# GSM.net
KiCad netlist of a schematic drawn in Altium Designer
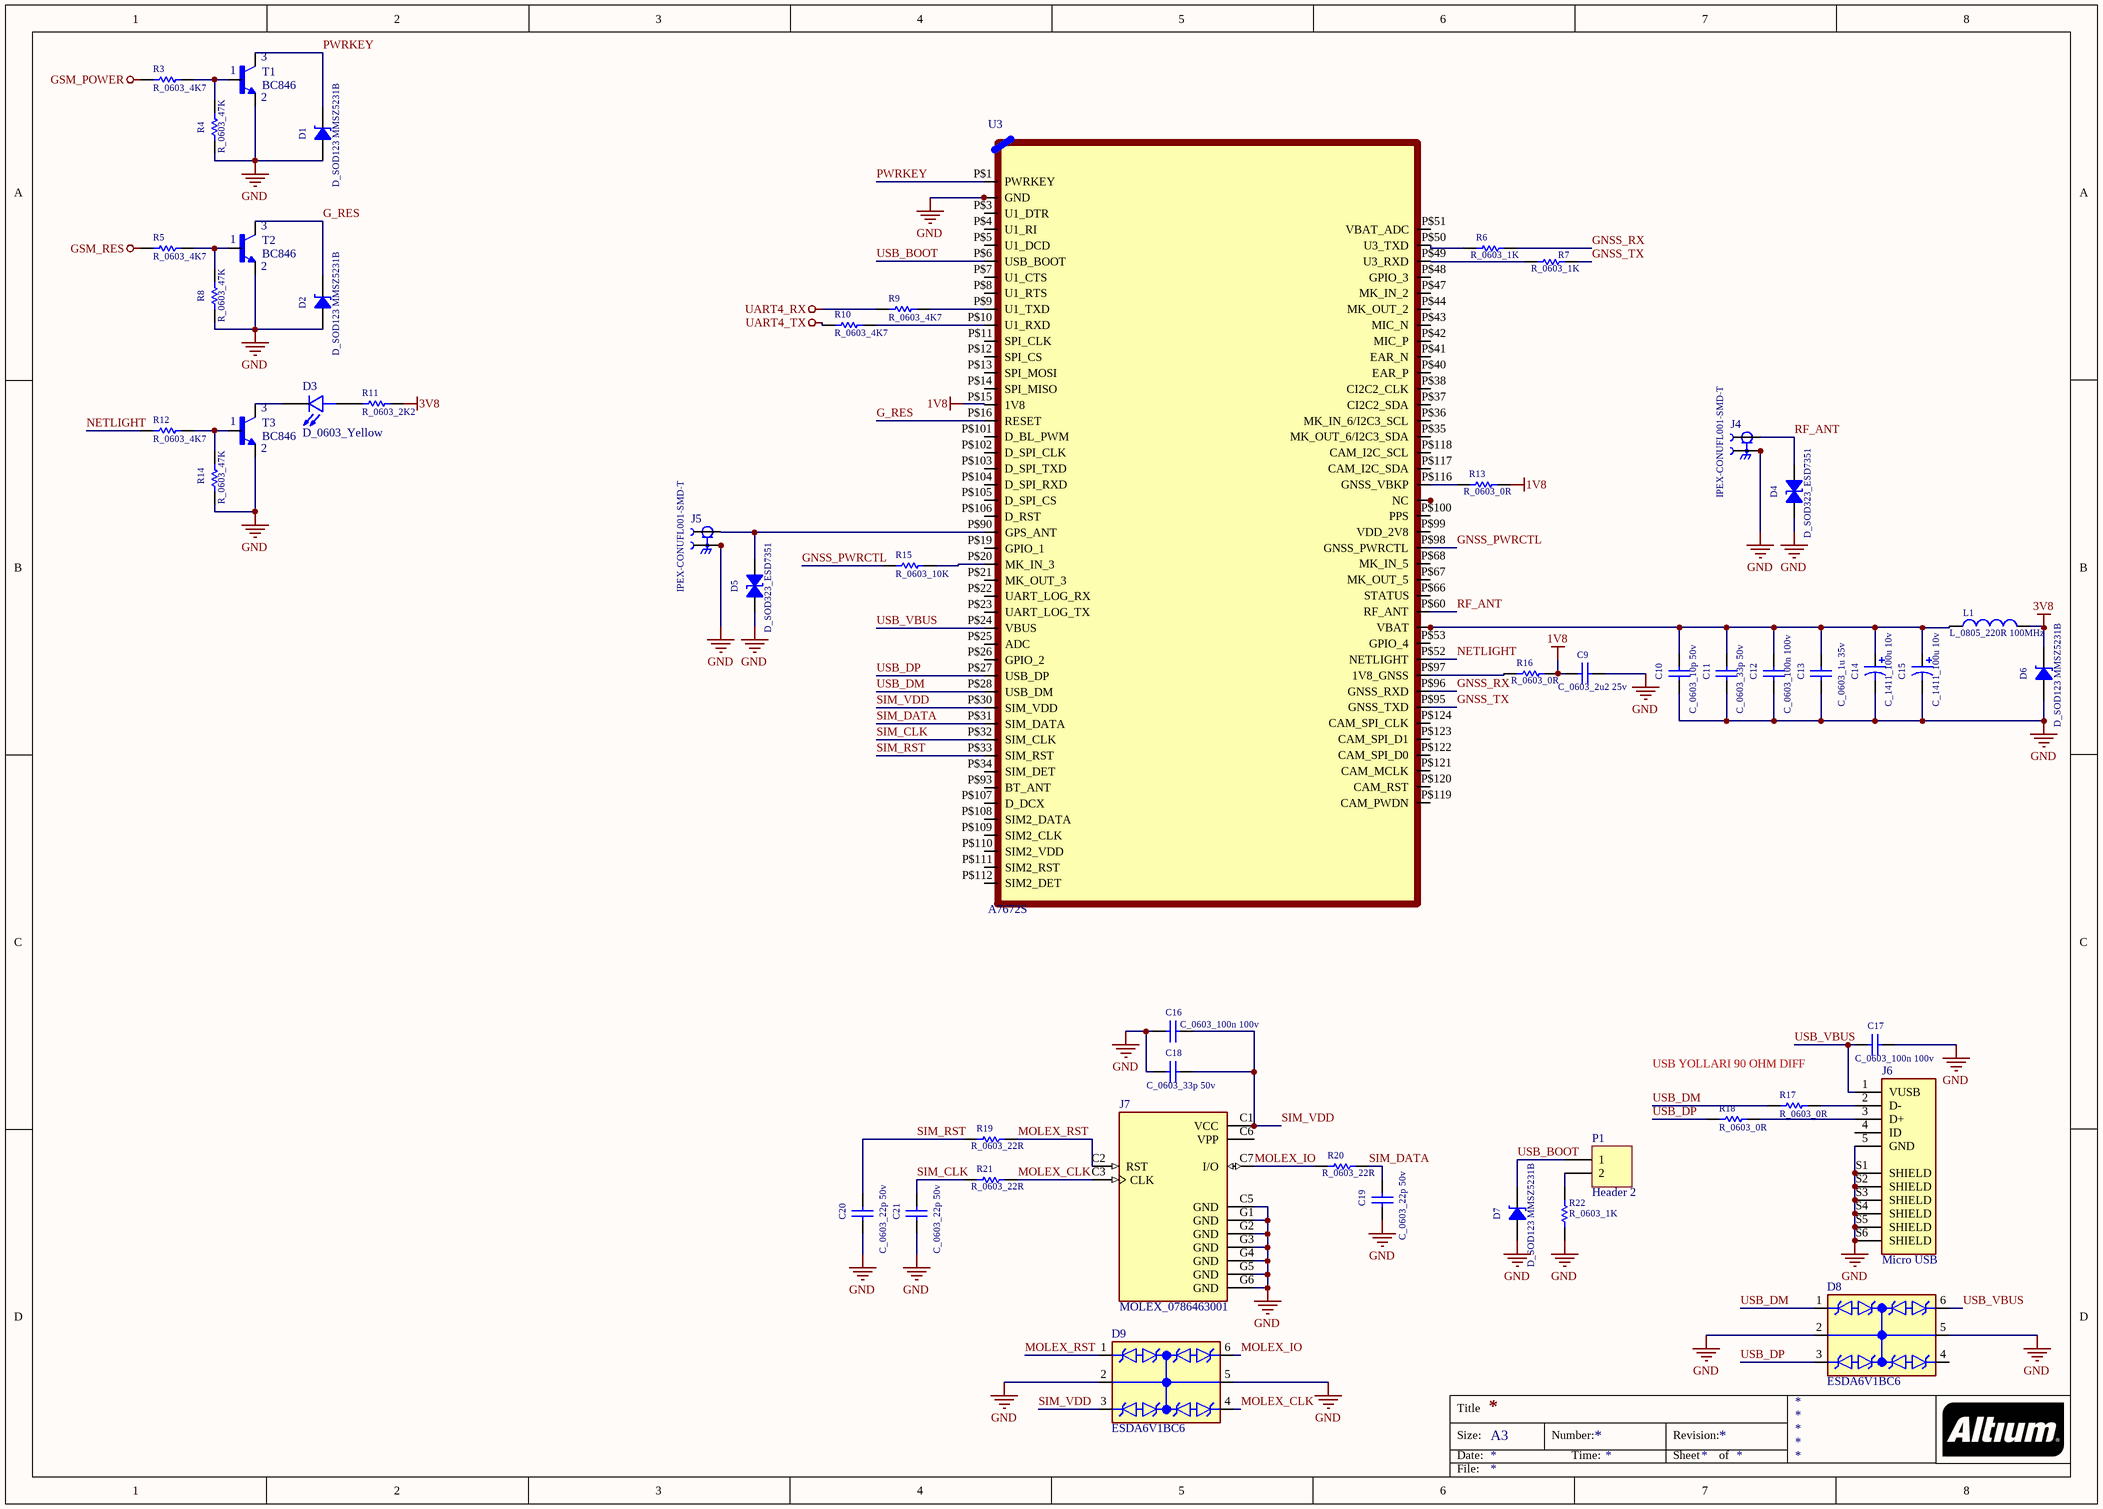
[diagram p0: GSM.SchDoc]

(export (version "E")
  (design (tool "Eeschema 10.0.6"))
  (components
    (comp (ref "C9")
      (value "C_0603_2u2 25v")
      (footprint "CAP 0603")
      (description "Capacitor")
      (fields (field (name "PUBLISHER") "Altium Limited"))
      (libsource (lib "HUE") (part "Cap"))
    )
    (comp (ref "C10")
      (value "C_0603_10p 50v")
      (footprint "CAP 0603")
      (description "Capacitor")
      (fields (field (name "PUBLISHER") "Altium Limited"))
      (libsource (lib "HUE") (part "Cap"))
    )
    (comp (ref "C11")
      (value "C_0603_33p 50v")
      (footprint "CAP 0603")
      (description "Capacitor")
      (fields (field (name "PUBLISHER") "Altium Limited"))
      (libsource (lib "HUE") (part "Cap"))
    )
    (comp (ref "C12")
      (value "C_0603_100n 100v")
      (footprint "CAP 0603")
      (description "Capacitor")
      (fields (field (name "PUBLISHER") "Altium Limited"))
      (libsource (lib "HUE") (part "Cap"))
    )
    (comp (ref "C13")
      (value "C_0603_1u 35v")
      (footprint "CAP 0603")
      (description "Capacitor")
      (fields (field (name "PUBLISHER") "Altium Limited"))
      (libsource (lib "HUE") (part "Cap"))
    )
    (comp (ref "C14")
      (value "C_1411_100u 10v")
      (footprint "CAP 1411 TAN")
      (description "Capacitor Tantalium")
      (fields (field (name "PUBLISHER") "Altium Limited"))
      (libsource (lib "HUE") (part "Cap Tantalium"))
    )
    (comp (ref "C15")
      (value "C_1411_100u 10v")
      (footprint "CAP 1411 TAN")
      (description "Capacitor Tantalium")
      (fields (field (name "PUBLISHER") "Altium Limited"))
      (libsource (lib "HUE") (part "Cap Tantalium"))
    )
    (comp (ref "C16")
      (value "C_0603_100n 100v")
      (footprint "CAP 0603")
      (description "Capacitor")
      (fields (field (name "PUBLISHER") "Altium Limited"))
      (libsource (lib "HUE") (part "Cap"))
    )
    (comp (ref "C17")
      (value "C_0603_100n 100v")
      (footprint "CAP 0603")
      (description "Capacitor")
      (fields (field (name "PUBLISHER") "Altium Limited"))
      (libsource (lib "HUE") (part "Cap"))
    )
    (comp (ref "C18")
      (value "C_0603_33p 50v")
      (footprint "CAP 0603")
      (description "Capacitor")
      (fields (field (name "PUBLISHER") "Altium Limited"))
      (libsource (lib "HUE") (part "Cap"))
    )
    (comp (ref "C19")
      (value "C_0603_22p 50v")
      (footprint "CAP 0603")
      (description "Capacitor")
      (fields (field (name "PUBLISHER") "Altium Limited"))
      (libsource (lib "HUE") (part "Cap"))
    )
    (comp (ref "C20")
      (value "C_0603_22p 50v")
      (footprint "CAP 0603")
      (description "Capacitor")
      (fields (field (name "PUBLISHER") "Altium Limited"))
      (libsource (lib "HUE") (part "Cap"))
    )
    (comp (ref "C21")
      (value "C_0603_22p 50v")
      (footprint "CAP 0603")
      (description "Capacitor")
      (fields (field (name "PUBLISHER") "Altium Limited"))
      (libsource (lib "HUE") (part "Cap"))
    )
    (comp (ref "D1")
      (value "D_SOD123 MMSZ5231B")
      (footprint "SOD-123")
      (description "Zener Diode")
      (libsource (lib "HUE") (part "Diode Zener"))
    )
    (comp (ref "D2")
      (value "D_SOD123 MMSZ5231B")
      (footprint "SOD-123")
      (description "Zener Diode")
      (libsource (lib "HUE") (part "Diode Zener"))
    )
    (comp (ref "D3")
      (value "D_0603_Yellow")
      (footprint "Led 0603")
      (description "Led")
      (fields (field (name "MP") "SML-D12FWT86") (field (name "MF") "Rohm"))
      (libsource (lib "HUE") (part "Led"))
    )
    (comp (ref "D4")
      (value "D_SOD323_ESD7351")
      (footprint "SOD323")
      (description "Zener Diode")
      (libsource (lib "HUE") (part "Diode TVS"))
    )
    (comp (ref "D5")
      (value "D_SOD323_ESD7351")
      (footprint "SOD323")
      (description "Zener Diode")
      (libsource (lib "HUE") (part "Diode TVS"))
    )
    (comp (ref "D6")
      (value "D_SOD123 MMSZ5231B")
      (footprint "SOD-123")
      (description "Zener Diode")
      (libsource (lib "HUE") (part "Diode Zener"))
    )
    (comp (ref "D7")
      (value "D_SOD123 MMSZ5231B")
      (footprint "SOD-123")
      (description "Zener Diode")
      (libsource (lib "HUE") (part "Diode Zener"))
    )
    (comp (ref "D8")
      (value "ESDA6V1BC6")
      (footprint "SOT23-6")
      (description "- Clamp - Ipp Tvs Diode Surface Mount SOT-23-6")
      (fields (field (name "MF") "STMicroelectronics"))
      (libsource (lib "HUE") (part "ESDA6V1BC6"))
    )
    (comp (ref "D9")
      (value "ESDA6V1BC6")
      (footprint "SOT23-6")
      (description "- Clamp - Ipp Tvs Diode Surface Mount SOT-23-6")
      (fields (field (name "MF") "STMicroelectronics"))
      (libsource (lib "HUE") (part "ESDA6V1BC6"))
    )
    (comp (ref "J4")
      (value "IPEX-CONUFL001-SMD-T")
      (footprint "IPEX_LINX_CONUFL001-SMD-T")
      (description "U.FL (UMCC) Connector Jack, Male Pin 50Ohm Surface Mount Solder")
      (fields (field (name "MP") "CONUFL001-SMD-T") (field (name "MF") "Linx"))
      (libsource (lib "HUE") (part "IPEX-CONUFL001-SMD-T"))
    )
    (comp (ref "J5")
      (value "IPEX-CONUFL001-SMD-T")
      (footprint "IPEX_LINX_CONUFL001-SMD-T")
      (description "U.FL (UMCC) Connector Jack, Male Pin 50Ohm Surface Mount Solder")
      (fields (field (name "MP") "CONUFL001-SMD-T") (field (name "MF") "Linx"))
      (libsource (lib "HUE") (part "IPEX-CONUFL001-SMD-T"))
    )
    (comp (ref "J6")
      (value "Micro USB")
      (footprint "Micro USB")
      (description "Micro USB 2.0, Input Output Connectors, B TYPE RECEPTACLE")
      (fields (field (name "MP") "10118193-0001LF") (field (name "MF") "Amphenol ICC"))
      (libsource (lib "HUE") (part "Micro USB"))
    )
    (comp (ref "J7")
      (value "MOLEX_0786463001")
      (footprint "MOLEX_0786463001")
      (description "6 Position Card Connector Micro SIM Surface Mount, Right Angle Gold")
      (fields (field (name "MF") "Molex") (field (name "MP") "0786463001"))
      (libsource (lib "HUE") (part "MOLEX_0786463001"))
    )
    (comp (ref "L1")
      (value "L_0805_220R 100MHz")
      (footprint "Inductor 0805")
      (description "Inductor")
      (fields (field (name "PUBLISHER") "Altium Limited"))
      (libsource (lib "HUE") (part "Inductor"))
    )
    (comp (ref "P1")
      (value "Header 2")
      (footprint "HDR1X2")
      (description "Header, 2-Pin")
      (fields (field (name "PUBLISHER") "Altium Limited"))
      (libsource (lib "Miscellaneous Connectors") (part "Header 2"))
    )
    (comp (ref "R3")
      (value "R_0603_4K7")
      (footprint "RES 0603")
      (description "Resistor")
      (fields (field (name "PUBLISHER") "Altium Limited"))
      (libsource (lib "HUE") (part "Res"))
    )
    (comp (ref "R4")
      (value "R_0603_47K")
      (footprint "RES 0603")
      (description "Resistor")
      (fields (field (name "PUBLISHER") "Altium Limited"))
      (libsource (lib "HUE") (part "Res"))
    )
    (comp (ref "R5")
      (value "R_0603_4K7")
      (footprint "RES 0603")
      (description "Resistor")
      (fields (field (name "PUBLISHER") "Altium Limited"))
      (libsource (lib "HUE") (part "Res"))
    )
    (comp (ref "R6")
      (value "R_0603_1K")
      (footprint "RES 0603")
      (description "Resistor")
      (fields (field (name "PUBLISHER") "Altium Limited"))
      (libsource (lib "HUE") (part "Res"))
    )
    (comp (ref "R7")
      (value "R_0603_1K")
      (footprint "RES 0603")
      (description "Resistor")
      (fields (field (name "PUBLISHER") "Altium Limited"))
      (libsource (lib "HUE") (part "Res"))
    )
    (comp (ref "R8")
      (value "R_0603_47K")
      (footprint "RES 0603")
      (description "Resistor")
      (fields (field (name "PUBLISHER") "Altium Limited"))
      (libsource (lib "HUE") (part "Res"))
    )
    (comp (ref "R9")
      (value "R_0603_4K7")
      (footprint "RES 0603")
      (description "Resistor")
      (fields (field (name "PUBLISHER") "Altium Limited"))
      (libsource (lib "HUE") (part "Res"))
    )
    (comp (ref "R10")
      (value "R_0603_4K7")
      (footprint "RES 0603")
      (description "Resistor")
      (fields (field (name "PUBLISHER") "Altium Limited"))
      (libsource (lib "HUE") (part "Res"))
    )
    (comp (ref "R11")
      (value "R_0603_2K2")
      (footprint "RES 0603")
      (description "Resistor")
      (fields (field (name "PUBLISHER") "Altium Limited"))
      (libsource (lib "HUE") (part "Res"))
    )
    (comp (ref "R12")
      (value "R_0603_4K7")
      (footprint "RES 0603")
      (description "Resistor")
      (fields (field (name "PUBLISHER") "Altium Limited"))
      (libsource (lib "HUE") (part "Res"))
    )
    (comp (ref "R13")
      (value "R_0603_0R")
      (footprint "RES 0603")
      (description "Resistor")
      (fields (field (name "PUBLISHER") "Altium Limited"))
      (libsource (lib "HUE") (part "Res"))
    )
    (comp (ref "R14")
      (value "R_0603_47K")
      (footprint "RES 0603")
      (description "Resistor")
      (fields (field (name "PUBLISHER") "Altium Limited"))
      (libsource (lib "HUE") (part "Res"))
    )
    (comp (ref "R15")
      (value "R_0603_10K")
      (footprint "RES 0603")
      (description "Resistor")
      (fields (field (name "PUBLISHER") "Altium Limited"))
      (libsource (lib "HUE") (part "Res"))
    )
    (comp (ref "R16")
      (value "R_0603_0R")
      (footprint "RES 0603")
      (description "Resistor")
      (fields (field (name "PUBLISHER") "Altium Limited"))
      (libsource (lib "HUE") (part "Res"))
    )
    (comp (ref "R17")
      (value "R_0603_0R")
      (footprint "RES 0603")
      (description "Resistor")
      (fields (field (name "PUBLISHER") "Altium Limited"))
      (libsource (lib "HUE") (part "Res"))
    )
    (comp (ref "R18")
      (value "R_0603_0R")
      (footprint "RES 0603")
      (description "Resistor")
      (fields (field (name "PUBLISHER") "Altium Limited"))
      (libsource (lib "HUE") (part "Res"))
    )
    (comp (ref "R19")
      (value "R_0603_22R")
      (footprint "RES 0603")
      (description "Resistor")
      (fields (field (name "PUBLISHER") "Altium Limited"))
      (libsource (lib "HUE") (part "Res"))
    )
    (comp (ref "R20")
      (value "R_0603_22R")
      (footprint "RES 0603")
      (description "Resistor")
      (fields (field (name "PUBLISHER") "Altium Limited"))
      (libsource (lib "HUE") (part "Res"))
    )
    (comp (ref "R21")
      (value "R_0603_22R")
      (footprint "RES 0603")
      (description "Resistor")
      (fields (field (name "PUBLISHER") "Altium Limited"))
      (libsource (lib "HUE") (part "Res"))
    )
    (comp (ref "R22")
      (value "R_0603_1K")
      (footprint "RES 0603")
      (description "Resistor")
      (fields (field (name "PUBLISHER") "Altium Limited"))
      (libsource (lib "HUE") (part "Res"))
    )
    (comp (ref "T1")
      (value "BC846")
      (footprint "SOT23")
      (fields (field (name "MF") "ON Semiconductor"))
      (libsource (lib "HUE") (part "BC846"))
    )
    (comp (ref "T2")
      (value "BC846")
      (footprint "SOT23")
      (fields (field (name "MF") "ON Semiconductor"))
      (libsource (lib "HUE") (part "BC846"))
    )
    (comp (ref "T3")
      (value "BC846")
      (footprint "SOT23")
      (fields (field (name "MF") "ON Semiconductor"))
      (libsource (lib "HUE") (part "BC846"))
    )
    (comp (ref "U3")
      (value "A7672S")
      (footprint "A7672S")
      (fields (field (name "MF") "SIMCom"))
      (libsource (lib "HUE") (part "A7672S"))
    )
  )
  (nets
    (net (code "1") (name "/GNSS_PWRCTL") (class "Default")
      (node (ref "R15") (pin "2") (pinfunction "2_2") (pintype "passive"))
      (node (ref "U3") (pin "P$98") (pinfunction "GNSS_PWRCTL_P$98") (pintype "bidirectional"))
    )
    (net (code "2") (name "/GNSS_RX") (class "Default")
      (node (ref "R6") (pin "1") (pinfunction "1_1") (pintype "passive"))
      (node (ref "U3") (pin "P$96") (pinfunction "GNSS_RXD_P$96") (pintype "bidirectional"))
    )
    (net (code "3") (name "/GNSS_TX") (class "Default")
      (node (ref "R7") (pin "1") (pinfunction "1_1") (pintype "passive"))
      (node (ref "U3") (pin "P$95") (pinfunction "GNSS_TXD_P$95") (pintype "bidirectional"))
    )
    (net (code "4") (name "/G_RES") (class "Default")
      (node (ref "D2") (pin "2") (pinfunction "2_2") (pintype "passive"))
      (node (ref "T2") (pin "3") (pinfunction "C_3") (pintype "passive"))
      (node (ref "U3") (pin "P$16") (pinfunction "RESET_P$16") (pintype "power_in"))
    )
    (net (code "5") (name "/MOLEX_CLK") (class "Default")
      (node (ref "D9") (pin "4") (pinfunction "C3_4") (pintype "passive"))
      (node (ref "J7") (pin "C3") (pinfunction "CLK_C3") (pintype "input"))
      (node (ref "R21") (pin "1") (pinfunction "1_1") (pintype "passive"))
    )
    (net (code "6") (name "/MOLEX_IO") (class "Default")
      (node (ref "D9") (pin "6") (pinfunction "C4_6") (pintype "passive"))
      (node (ref "J7") (pin "C7") (pinfunction "I/O_C7") (pintype "bidirectional"))
      (node (ref "R20") (pin "2") (pinfunction "2_2") (pintype "passive"))
    )
    (net (code "7") (name "/MOLEX_RST") (class "Default")
      (node (ref "D9") (pin "1") (pinfunction "C1_1") (pintype "passive"))
      (node (ref "J7") (pin "C2") (pinfunction "RST_C2") (pintype "input"))
      (node (ref "R19") (pin "1") (pinfunction "1_1") (pintype "passive"))
    )
    (net (code "8") (name "/NETLIGHT") (class "Default")
      (node (ref "R12") (pin "2") (pinfunction "2_2") (pintype "passive"))
      (node (ref "U3") (pin "P$52") (pinfunction "NETLIGHT_P$52") (pintype "bidirectional"))
    )
    (net (code "9") (name "/PWRKEY") (class "Default")
      (node (ref "D1") (pin "2") (pinfunction "2_2") (pintype "passive"))
      (node (ref "T1") (pin "3") (pinfunction "C_3") (pintype "passive"))
      (node (ref "U3") (pin "P$1") (pinfunction "PWRKEY_P$1") (pintype "power_in"))
    )
    (net (code "10") (name "/RF_ANT") (class "Default")
      (node (ref "D4") (pin "2") (pinfunction "2_2") (pintype "passive"))
      (node (ref "J4") (pin "1") (pinfunction "1_1") (pintype "passive"))
      (node (ref "U3") (pin "P$60") (pinfunction "RF_ANT_P$60") (pintype "bidirectional"))
    )
    (net (code "11") (name "/SIM_CLK") (class "Default")
      (node (ref "C21") (pin "1") (pinfunction "1_1") (pintype "passive"))
      (node (ref "R21") (pin "2") (pinfunction "2_2") (pintype "passive"))
      (node (ref "U3") (pin "P$32") (pinfunction "SIM_CLK_P$32") (pintype "bidirectional"))
    )
    (net (code "12") (name "/SIM_DATA") (class "Default")
      (node (ref "C19") (pin "1") (pinfunction "1_1") (pintype "passive"))
      (node (ref "R20") (pin "1") (pinfunction "1_1") (pintype "passive"))
      (node (ref "U3") (pin "P$31") (pinfunction "SIM_DATA_P$31") (pintype "bidirectional"))
    )
    (net (code "13") (name "/SIM_RST") (class "Default")
      (node (ref "C20") (pin "1") (pinfunction "1_1") (pintype "passive"))
      (node (ref "R19") (pin "2") (pinfunction "2_2") (pintype "passive"))
      (node (ref "U3") (pin "P$33") (pinfunction "SIM_RST_P$33") (pintype "bidirectional"))
    )
    (net (code "14") (name "/SIM_VDD") (class "Default")
      (node (ref "C16") (pin "1") (pinfunction "1_1") (pintype "passive"))
      (node (ref "C18") (pin "1") (pinfunction "1_1") (pintype "passive"))
      (node (ref "D9") (pin "3") (pinfunction "C2_3") (pintype "passive"))
      (node (ref "J7") (pin "C1") (pinfunction "VCC_C1") (pintype "power_in"))
      (node (ref "U3") (pin "P$30") (pinfunction "SIM_VDD_P$30") (pintype "bidirectional"))
    )
    (net (code "15") (name "/USB_BOOT") (class "Default")
      (node (ref "D7") (pin "2") (pinfunction "2_2") (pintype "passive"))
      (node (ref "P1") (pin "1") (pinfunction "1_1") (pintype "passive"))
      (node (ref "U3") (pin "P$6") (pinfunction "USB_BOOT_P$6") (pintype "bidirectional"))
    )
    (net (code "16") (name "/USB_DM") (class "Default")
      (node (ref "D8") (pin "1") (pinfunction "C1_1") (pintype "passive"))
      (node (ref "R17") (pin "2") (pinfunction "2_2") (pintype "passive"))
      (node (ref "U3") (pin "P$28") (pinfunction "USB_DM_P$28") (pintype "bidirectional"))
    )
    (net (code "17") (name "/USB_DP") (class "Default")
      (node (ref "D8") (pin "3") (pinfunction "C2_3") (pintype "passive"))
      (node (ref "R18") (pin "2") (pinfunction "2_2") (pintype "passive"))
      (node (ref "U3") (pin "P$27") (pinfunction "USB_DP_P$27") (pintype "bidirectional"))
    )
    (net (code "18") (name "/USB_VBUS") (class "Default")
      (node (ref "C17") (pin "2") (pinfunction "2_2") (pintype "passive"))
      (node (ref "D8") (pin "6") (pinfunction "C4_6") (pintype "passive"))
      (node (ref "J6") (pin "1") (pinfunction "VUSB_1") (pintype "passive"))
      (node (ref "U3") (pin "P$24") (pinfunction "VBUS_P$24") (pintype "bidirectional"))
    )
    (net (code "19") (name "1V8") (class "Default")
      (node (ref "C9") (pin "1") (pinfunction "1_1") (pintype "passive"))
      (node (ref "R13") (pin "1") (pinfunction "1_1") (pintype "passive"))
      (node (ref "R16") (pin "1") (pinfunction "1_1") (pintype "passive"))
      (node (ref "U3") (pin "P$15") (pinfunction "1V8_P$15") (pintype "power_in"))
    )
    (net (code "20") (name "3V8") (class "Default")
      (node (ref "D6") (pin "2") (pinfunction "2_2") (pintype "passive"))
      (node (ref "L1") (pin "2") (pinfunction "2_2") (pintype "passive"))
      (node (ref "R11") (pin "2") (pinfunction "2_2") (pintype "passive"))
    )
    (net (code "21") (name "GND") (class "Default")
      (node (ref "C10") (pin "1") (pinfunction "1_1") (pintype "passive"))
      (node (ref "C11") (pin "1") (pinfunction "1_1") (pintype "passive"))
      (node (ref "C12") (pin "1") (pinfunction "1_1") (pintype "passive"))
      (node (ref "C13") (pin "2") (pinfunction "2_2") (pintype "passive"))
      (node (ref "C14") (pin "2") (pinfunction "2_2") (pintype "passive"))
      (node (ref "C15") (pin "2") (pinfunction "2_2") (pintype "passive"))
      (node (ref "C16") (pin "2") (pinfunction "2_2") (pintype "passive"))
      (node (ref "C17") (pin "1") (pinfunction "1_1") (pintype "passive"))
      (node (ref "C18") (pin "2") (pinfunction "2_2") (pintype "passive"))
      (node (ref "C19") (pin "2") (pinfunction "2_2") (pintype "passive"))
      (node (ref "C20") (pin "2") (pinfunction "2_2") (pintype "passive"))
      (node (ref "C21") (pin "2") (pinfunction "2_2") (pintype "passive"))
      (node (ref "C9") (pin "2") (pinfunction "2_2") (pintype "passive"))
      (node (ref "D1") (pin "1") (pinfunction "1_1") (pintype "passive"))
      (node (ref "D2") (pin "1") (pinfunction "1_1") (pintype "passive"))
      (node (ref "D4") (pin "1") (pinfunction "1_1") (pintype "passive"))
      (node (ref "D5") (pin "1") (pinfunction "1_1") (pintype "passive"))
      (node (ref "D6") (pin "1") (pinfunction "1_1") (pintype "passive"))
      (node (ref "D7") (pin "1") (pinfunction "1_1") (pintype "passive"))
      (node (ref "D8") (pin "2") (pinfunction "CC1_2") (pintype "passive"))
      (node (ref "D8") (pin "5") (pinfunction "CC2_5") (pintype "passive"))
      (node (ref "D9") (pin "2") (pinfunction "CC1_2") (pintype "passive"))
      (node (ref "D9") (pin "5") (pinfunction "CC2_5") (pintype "passive"))
      (node (ref "J4") (pin "2") (pinfunction "2_2") (pintype "passive"))
      (node (ref "J4") (pin "3") (pinfunction "2_3") (pintype "passive"))
      (node (ref "J5") (pin "2") (pinfunction "2_2") (pintype "passive"))
      (node (ref "J5") (pin "3") (pinfunction "2_3") (pintype "passive"))
      (node (ref "J6") (pin "5") (pinfunction "GND_5") (pintype "passive"))
      (node (ref "J6") (pin "S1") (pinfunction "SHIELD_S1") (pintype "passive"))
      (node (ref "J6") (pin "S2") (pinfunction "SHIELD_S2") (pintype "passive"))
      (node (ref "J6") (pin "S3") (pinfunction "SHIELD_S3") (pintype "passive"))
      (node (ref "J6") (pin "S4") (pinfunction "SHIELD_S4") (pintype "passive"))
      (node (ref "J6") (pin "S5") (pinfunction "SHIELD_S5") (pintype "passive"))
      (node (ref "J6") (pin "S6") (pinfunction "SHIELD_S6") (pintype "passive"))
      (node (ref "J7") (pin "C5") (pinfunction "GND_C5") (pintype "power_in"))
      (node (ref "J7") (pin "G1") (pinfunction "GND_G1") (pintype "power_in"))
      (node (ref "J7") (pin "G2") (pinfunction "GND_G2") (pintype "power_in"))
      (node (ref "J7") (pin "G3") (pinfunction "GND_G3") (pintype "power_in"))
      (node (ref "J7") (pin "G4") (pinfunction "GND_G4") (pintype "power_in"))
      (node (ref "J7") (pin "G5") (pinfunction "GND_G5") (pintype "power_in"))
      (node (ref "J7") (pin "G6") (pinfunction "GND_G6") (pintype "power_in"))
      (node (ref "R14") (pin "2") (pinfunction "2_2") (pintype "passive"))
      (node (ref "R22") (pin "2") (pinfunction "2_2") (pintype "passive"))
      (node (ref "R4") (pin "2") (pinfunction "2_2") (pintype "passive"))
      (node (ref "R8") (pin "2") (pinfunction "2_2") (pintype "passive"))
      (node (ref "T1") (pin "2") (pinfunction "E_2") (pintype "passive"))
      (node (ref "T2") (pin "2") (pinfunction "E_2") (pintype "passive"))
      (node (ref "T3") (pin "2") (pinfunction "E_2") (pintype "passive"))
      (node (ref "U3") (pin "P$17") (pinfunction "GND_P$17") (pintype "power_in"))
      (node (ref "U3") (pin "P$18") (pinfunction "GND_P$18") (pintype "power_in"))
      (node (ref "U3") (pin "P$2") (pinfunction "GND_P$2") (pintype "power_in"))
      (node (ref "U3") (pin "P$29") (pinfunction "GND_P$29") (pintype "power_in"))
      (node (ref "U3") (pin "P$39") (pinfunction "GND_P$39") (pintype "power_in"))
      (node (ref "U3") (pin "P$45") (pinfunction "GND_P$45") (pintype "power_in"))
      (node (ref "U3") (pin "P$46") (pinfunction "GND_P$46") (pintype "power_in"))
      (node (ref "U3") (pin "P$54") (pinfunction "GND_P$54") (pintype "power_in"))
      (node (ref "U3") (pin "P$58") (pinfunction "GND_P$58") (pintype "power_in"))
      (node (ref "U3") (pin "P$59") (pinfunction "GND_P$59") (pintype "power_in"))
      (node (ref "U3") (pin "P$61") (pinfunction "GND_P$61") (pintype "power_in"))
      (node (ref "U3") (pin "P$62") (pinfunction "GND_P$62") (pintype "power_in"))
      (node (ref "U3") (pin "P$63") (pinfunction "GND_P$63") (pintype "power_in"))
      (node (ref "U3") (pin "P$64") (pinfunction "GND_P$64") (pintype "power_in"))
      (node (ref "U3") (pin "P$65") (pinfunction "GND_P$65") (pintype "power_in"))
      (node (ref "U3") (pin "P$69") (pinfunction "GND_P$69") (pintype "power_in"))
      (node (ref "U3") (pin "P$70") (pinfunction "GND_P$70") (pintype "power_in"))
      (node (ref "U3") (pin "P$71") (pinfunction "GND_P$71") (pintype "power_in"))
      (node (ref "U3") (pin "P$72") (pinfunction "GND_P$72") (pintype "power_in"))
      (node (ref "U3") (pin "P$73") (pinfunction "GND_P$73") (pintype "power_in"))
      (node (ref "U3") (pin "P$74") (pinfunction "GND_P$74") (pintype "power_in"))
      (node (ref "U3") (pin "P$75") (pinfunction "GND_P$75") (pintype "power_in"))
      (node (ref "U3") (pin "P$76") (pinfunction "GND_P$76") (pintype "power_in"))
      (node (ref "U3") (pin "P$77") (pinfunction "GND_P$77") (pintype "power_in"))
      (node (ref "U3") (pin "P$78") (pinfunction "GND_P$78") (pintype "power_in"))
      (node (ref "U3") (pin "P$79") (pinfunction "GND_P$79") (pintype "power_in"))
      (node (ref "U3") (pin "P$80") (pinfunction "GND_P$80") (pintype "power_in"))
      (node (ref "U3") (pin "P$81") (pinfunction "GND_P$81") (pintype "power_in"))
      (node (ref "U3") (pin "P$82") (pinfunction "GND_P$82") (pintype "power_in"))
      (node (ref "U3") (pin "P$83") (pinfunction "GND_P$83") (pintype "power_in"))
      (node (ref "U3") (pin "P$84") (pinfunction "GND_P$84") (pintype "power_in"))
      (node (ref "U3") (pin "P$85") (pinfunction "GND_P$85") (pintype "power_in"))
      (node (ref "U3") (pin "P$86") (pinfunction "GND_P$86") (pintype "power_in"))
      (node (ref "U3") (pin "P$87") (pinfunction "GND_P$87") (pintype "power_in"))
      (node (ref "U3") (pin "P$88") (pinfunction "GND_P$88") (pintype "power_in"))
      (node (ref "U3") (pin "P$89") (pinfunction "GND_P$89") (pintype "power_in"))
      (node (ref "U3") (pin "P$91") (pinfunction "GND_P$91") (pintype "power_in"))
      (node (ref "U3") (pin "P$92") (pinfunction "GND_P$92") (pintype "power_in"))
      (node (ref "U3") (pin "P$94") (pinfunction "GND_P$94") (pintype "power_in"))
    )
    (net (code "22") (name "GSM_POWER") (class "Default")
      (node (ref "R3") (pin "2") (pinfunction "2_2") (pintype "passive"))
    )
    (net (code "23") (name "GSM_RES") (class "Default")
      (node (ref "R5") (pin "2") (pinfunction "2_2") (pintype "passive"))
    )
    (net (code "24") (name "Net-(C10-Pad2)") (class "Default")
      (node (ref "C10") (pin "2") (pinfunction "2_2") (pintype "passive"))
      (node (ref "C11") (pin "2") (pinfunction "2_2") (pintype "passive"))
      (node (ref "C12") (pin "2") (pinfunction "2_2") (pintype "passive"))
      (node (ref "C13") (pin "1") (pinfunction "1_1") (pintype "passive"))
      (node (ref "C14") (pin "1") (pinfunction "1_1") (pintype "passive"))
      (node (ref "C15") (pin "1") (pinfunction "1_1") (pintype "passive"))
      (node (ref "L1") (pin "1") (pinfunction "1_1") (pintype "passive"))
      (node (ref "U3") (pin "P$55") (pinfunction "VBAT_P$55") (pintype "bidirectional"))
      (node (ref "U3") (pin "P$56") (pinfunction "VBAT_P$56") (pintype "bidirectional"))
      (node (ref "U3") (pin "P$57") (pinfunction "VBAT_P$57") (pintype "bidirectional"))
    )
    (net (code "25") (name "Net-(D3-A)") (class "Default")
      (node (ref "D3") (pin "1") (pinfunction "A_1") (pintype "passive"))
      (node (ref "R11") (pin "1") (pinfunction "1_1") (pintype "passive"))
    )
    (net (code "26") (name "Net-(D3-C)") (class "Default")
      (node (ref "D3") (pin "2") (pinfunction "C_2") (pintype "passive"))
      (node (ref "T3") (pin "3") (pinfunction "C_3") (pintype "passive"))
    )
    (net (code "27") (name "Net-(J6-D+)") (class "Default")
      (node (ref "J6") (pin "3") (pinfunction "D+_3") (pintype "passive"))
      (node (ref "R18") (pin "1") (pinfunction "1_1") (pintype "passive"))
    )
    (net (code "28") (name "Net-(J6-D-)") (class "Default")
      (node (ref "J6") (pin "2") (pinfunction "D-_2") (pintype "passive"))
      (node (ref "R17") (pin "1") (pinfunction "1_1") (pintype "passive"))
    )
    (net (code "29") (name "Net-(P1-Pad2)") (class "Default")
      (node (ref "P1") (pin "2") (pinfunction "2_2") (pintype "passive"))
      (node (ref "R22") (pin "1") (pinfunction "1_1") (pintype "passive"))
    )
    (net (code "30") (name "Net-(T1-B)") (class "Default")
      (node (ref "R3") (pin "1") (pinfunction "1_1") (pintype "passive"))
      (node (ref "R4") (pin "1") (pinfunction "1_1") (pintype "passive"))
      (node (ref "T1") (pin "1") (pinfunction "B_1") (pintype "passive"))
    )
    (net (code "31") (name "Net-(T2-B)") (class "Default")
      (node (ref "R5") (pin "1") (pinfunction "1_1") (pintype "passive"))
      (node (ref "R8") (pin "1") (pinfunction "1_1") (pintype "passive"))
      (node (ref "T2") (pin "1") (pinfunction "B_1") (pintype "passive"))
    )
    (net (code "32") (name "Net-(T3-B)") (class "Default")
      (node (ref "R12") (pin "1") (pinfunction "1_1") (pintype "passive"))
      (node (ref "R14") (pin "1") (pinfunction "1_1") (pintype "passive"))
      (node (ref "T3") (pin "1") (pinfunction "B_1") (pintype "passive"))
    )
    (net (code "33") (name "Net-(U3-1V8_GNSS)") (class "Default")
      (node (ref "R16") (pin "2") (pinfunction "2_2") (pintype "passive"))
      (node (ref "U3") (pin "P$97") (pinfunction "1V8_GNSS_P$97") (pintype "bidirectional"))
    )
    (net (code "34") (name "Net-(U3-GNSS_VBKP)") (class "Default")
      (node (ref "R13") (pin "2") (pinfunction "2_2") (pintype "passive"))
      (node (ref "U3") (pin "P$116") (pinfunction "GNSS_VBKP_P$116") (pintype "bidirectional"))
    )
    (net (code "35") (name "Net-(U3-GPS_ANT)") (class "Default")
      (node (ref "D5") (pin "2") (pinfunction "2_2") (pintype "passive"))
      (node (ref "J5") (pin "1") (pinfunction "1_1") (pintype "passive"))
      (node (ref "U3") (pin "P$90") (pinfunction "GPS_ANT_P$90") (pintype "bidirectional"))
    )
    (net (code "36") (name "Net-(U3-MK_IN_3)") (class "Default")
      (node (ref "R15") (pin "1") (pinfunction "1_1") (pintype "passive"))
      (node (ref "U3") (pin "P$20") (pinfunction "MK_IN_3_P$20") (pintype "bidirectional"))
    )
    (net (code "37") (name "Net-(U3-NC-PadP$113)") (class "Default")
      (node (ref "U3") (pin "P$113") (pinfunction "NC_P$113") (pintype "bidirectional"))
      (node (ref "U3") (pin "P$114") (pinfunction "NC_P$114") (pintype "bidirectional"))
      (node (ref "U3") (pin "P$115") (pinfunction "NC_P$115") (pintype "bidirectional"))
    )
    (net (code "38") (name "Net-(U3-U1_RXD)") (class "Default")
      (node (ref "R10") (pin "1") (pinfunction "1_1") (pintype "passive"))
      (node (ref "U3") (pin "P$10") (pinfunction "U1_RXD_P$10") (pintype "bidirectional"))
    )
    (net (code "39") (name "Net-(U3-U1_TXD)") (class "Default")
      (node (ref "R9") (pin "1") (pinfunction "1_1") (pintype "passive"))
      (node (ref "U3") (pin "P$9") (pinfunction "U1_TXD_P$9") (pintype "bidirectional"))
    )
    (net (code "40") (name "Net-(U3-U3_RXD)") (class "Default")
      (node (ref "R7") (pin "2") (pinfunction "2_2") (pintype "passive"))
      (node (ref "U3") (pin "P$49") (pinfunction "U3_RXD_P$49") (pintype "bidirectional"))
    )
    (net (code "41") (name "Net-(U3-U3_TXD)") (class "Default")
      (node (ref "R6") (pin "2") (pinfunction "2_2") (pintype "passive"))
      (node (ref "U3") (pin "P$50") (pinfunction "U3_TXD_P$50") (pintype "bidirectional"))
    )
    (net (code "42") (name "UART4_RX") (class "Default")
      (node (ref "R9") (pin "2") (pinfunction "2_2") (pintype "passive"))
    )
    (net (code "43") (name "UART4_TX") (class "Default")
      (node (ref "R10") (pin "2") (pinfunction "2_2") (pintype "passive"))
    )
    (net (code "44") (name "unconnected-(D8-C3-Pad4)") (class "Default")
      (node (ref "D8") (pin "4") (pinfunction "C3_4") (pintype "passive"))
    )
    (net (code "45") (name "unconnected-(J6-ID-Pad4)") (class "Default")
      (node (ref "J6") (pin "4") (pinfunction "ID_4") (pintype "passive"))
    )
    (net (code "46") (name "unconnected-(J7-VPP-PadC6)") (class "Default")
      (node (ref "J7") (pin "C6") (pinfunction "VPP_C6") (pintype "power_in"))
    )
    (net (code "47") (name "unconnected-(U3-ADC-PadP$25)") (class "Default")
      (node (ref "U3") (pin "P$25") (pinfunction "ADC_P$25") (pintype "bidirectional"))
    )
    (net (code "48") (name "unconnected-(U3-BT_ANT-PadP$93)") (class "Default")
      (node (ref "U3") (pin "P$93") (pinfunction "BT_ANT_P$93") (pintype "bidirectional"))
    )
    (net (code "49") (name "unconnected-(U3-CAM_I2C_SCL-PadP$118)") (class "Default")
      (node (ref "U3") (pin "P$118") (pinfunction "CAM_I2C_SCL_P$118") (pintype "bidirectional"))
    )
    (net (code "50") (name "unconnected-(U3-CAM_I2C_SDA-PadP$117)") (class "Default")
      (node (ref "U3") (pin "P$117") (pinfunction "CAM_I2C_SDA_P$117") (pintype "bidirectional"))
    )
    (net (code "51") (name "unconnected-(U3-CAM_MCLK-PadP$121)") (class "Default")
      (node (ref "U3") (pin "P$121") (pinfunction "CAM_MCLK_P$121") (pintype "bidirectional"))
    )
    (net (code "52") (name "unconnected-(U3-CAM_PWDN-PadP$119)") (class "Default")
      (node (ref "U3") (pin "P$119") (pinfunction "CAM_PWDN_P$119") (pintype "bidirectional"))
    )
    (net (code "53") (name "unconnected-(U3-CAM_RST-PadP$120)") (class "Default")
      (node (ref "U3") (pin "P$120") (pinfunction "CAM_RST_P$120") (pintype "bidirectional"))
    )
    (net (code "54") (name "unconnected-(U3-CAM_SPI_CLK-PadP$124)") (class "Default")
      (node (ref "U3") (pin "P$124") (pinfunction "CAM_SPI_CLK_P$124") (pintype "bidirectional"))
    )
    (net (code "55") (name "unconnected-(U3-CAM_SPI_D0-PadP$122)") (class "Default")
      (node (ref "U3") (pin "P$122") (pinfunction "CAM_SPI_D0_P$122") (pintype "bidirectional"))
    )
    (net (code "56") (name "unconnected-(U3-CAM_SPI_D1-PadP$123)") (class "Default")
      (node (ref "U3") (pin "P$123") (pinfunction "CAM_SPI_D1_P$123") (pintype "bidirectional"))
    )
    (net (code "57") (name "unconnected-(U3-CI2C2_CLK-PadP$38)") (class "Default")
      (node (ref "U3") (pin "P$38") (pinfunction "CI2C2_CLK_P$38") (pintype "bidirectional"))
    )
    (net (code "58") (name "unconnected-(U3-CI2C2_SDA-PadP$37)") (class "Default")
      (node (ref "U3") (pin "P$37") (pinfunction "CI2C2_SDA_P$37") (pintype "bidirectional"))
    )
    (net (code "59") (name "unconnected-(U3-D_BL_PWM-PadP$101)") (class "Default")
      (node (ref "U3") (pin "P$101") (pinfunction "D_BL_PWM_P$101") (pintype "bidirectional"))
    )
    (net (code "60") (name "unconnected-(U3-D_DCX-PadP$107)") (class "Default")
      (node (ref "U3") (pin "P$107") (pinfunction "D_DCX_P$107") (pintype "bidirectional"))
    )
    (net (code "61") (name "unconnected-(U3-D_RST-PadP$106)") (class "Default")
      (node (ref "U3") (pin "P$106") (pinfunction "D_RST_P$106") (pintype "bidirectional"))
    )
    (net (code "62") (name "unconnected-(U3-D_SPI_CLK-PadP$102)") (class "Default")
      (node (ref "U3") (pin "P$102") (pinfunction "D_SPI_CLK_P$102") (pintype "bidirectional"))
    )
    (net (code "63") (name "unconnected-(U3-D_SPI_CS-PadP$105)") (class "Default")
      (node (ref "U3") (pin "P$105") (pinfunction "D_SPI_CS_P$105") (pintype "bidirectional"))
    )
    (net (code "64") (name "unconnected-(U3-D_SPI_RXD-PadP$104)") (class "Default")
      (node (ref "U3") (pin "P$104") (pinfunction "D_SPI_RXD_P$104") (pintype "bidirectional"))
    )
    (net (code "65") (name "unconnected-(U3-D_SPI_TXD-PadP$103)") (class "Default")
      (node (ref "U3") (pin "P$103") (pinfunction "D_SPI_TXD_P$103") (pintype "bidirectional"))
    )
    (net (code "66") (name "unconnected-(U3-EAR_N-PadP$41)") (class "Default")
      (node (ref "U3") (pin "P$41") (pinfunction "EAR_N_P$41") (pintype "bidirectional"))
    )
    (net (code "67") (name "unconnected-(U3-EAR_P-PadP$40)") (class "Default")
      (node (ref "U3") (pin "P$40") (pinfunction "EAR_P_P$40") (pintype "bidirectional"))
    )
    (net (code "68") (name "unconnected-(U3-GPIO_1-PadP$19)") (class "Default")
      (node (ref "U3") (pin "P$19") (pinfunction "GPIO_1_P$19") (pintype "bidirectional"))
    )
    (net (code "69") (name "unconnected-(U3-GPIO_2-PadP$26)") (class "Default")
      (node (ref "U3") (pin "P$26") (pinfunction "GPIO_2_P$26") (pintype "bidirectional"))
    )
    (net (code "70") (name "unconnected-(U3-GPIO_3-PadP$48)") (class "Default")
      (node (ref "U3") (pin "P$48") (pinfunction "GPIO_3_P$48") (pintype "bidirectional"))
    )
    (net (code "71") (name "unconnected-(U3-GPIO_4-PadP$53)") (class "Default")
      (node (ref "U3") (pin "P$53") (pinfunction "GPIO_4_P$53") (pintype "bidirectional"))
    )
    (net (code "72") (name "unconnected-(U3-MIC_N-PadP$43)") (class "Default")
      (node (ref "U3") (pin "P$43") (pinfunction "MIC_N_P$43") (pintype "bidirectional"))
    )
    (net (code "73") (name "unconnected-(U3-MIC_P-PadP$42)") (class "Default")
      (node (ref "U3") (pin "P$42") (pinfunction "MIC_P_P$42") (pintype "bidirectional"))
    )
    (net (code "74") (name "unconnected-(U3-MK_IN_2-PadP$47)") (class "Default")
      (node (ref "U3") (pin "P$47") (pinfunction "MK_IN_2_P$47") (pintype "bidirectional"))
    )
    (net (code "75") (name "unconnected-(U3-MK_IN_5-PadP$68)") (class "Default")
      (node (ref "U3") (pin "P$68") (pinfunction "MK_IN_5_P$68") (pintype "bidirectional"))
    )
    (net (code "76") (name "unconnected-(U3-MK_IN_6{slash}I2C3_SCL-PadP$36)") (class "Default")
      (node (ref "U3") (pin "P$36") (pinfunction "MK_IN_6/I2C3_SCL_P$36") (pintype "bidirectional"))
    )
    (net (code "77") (name "unconnected-(U3-MK_OUT_2-PadP$44)") (class "Default")
      (node (ref "U3") (pin "P$44") (pinfunction "MK_OUT_2_P$44") (pintype "bidirectional"))
    )
    (net (code "78") (name "unconnected-(U3-MK_OUT_3-PadP$21)") (class "Default")
      (node (ref "U3") (pin "P$21") (pinfunction "MK_OUT_3_P$21") (pintype "bidirectional"))
    )
    (net (code "79") (name "unconnected-(U3-MK_OUT_5-PadP$67)") (class "Default")
      (node (ref "U3") (pin "P$67") (pinfunction "MK_OUT_5_P$67") (pintype "bidirectional"))
    )
    (net (code "80") (name "unconnected-(U3-MK_OUT_6{slash}I2C3_SDA-PadP$35)") (class "Default")
      (node (ref "U3") (pin "P$35") (pinfunction "MK_OUT_6/I2C3_SDA_P$35") (pintype "bidirectional"))
    )
    (net (code "81") (name "unconnected-(U3-PPS-PadP$100)") (class "Default")
      (node (ref "U3") (pin "P$100") (pinfunction "PPS_P$100") (pintype "bidirectional"))
    )
    (net (code "82") (name "unconnected-(U3-SIM2_CLK-PadP$109)") (class "Default")
      (node (ref "U3") (pin "P$109") (pinfunction "SIM2_CLK_P$109") (pintype "bidirectional"))
    )
    (net (code "83") (name "unconnected-(U3-SIM2_DATA-PadP$108)") (class "Default")
      (node (ref "U3") (pin "P$108") (pinfunction "SIM2_DATA_P$108") (pintype "bidirectional"))
    )
    (net (code "84") (name "unconnected-(U3-SIM2_DET-PadP$112)") (class "Default")
      (node (ref "U3") (pin "P$112") (pinfunction "SIM2_DET_P$112") (pintype "bidirectional"))
    )
    (net (code "85") (name "unconnected-(U3-SIM2_RST-PadP$111)") (class "Default")
      (node (ref "U3") (pin "P$111") (pinfunction "SIM2_RST_P$111") (pintype "bidirectional"))
    )
    (net (code "86") (name "unconnected-(U3-SIM2_VDD-PadP$110)") (class "Default")
      (node (ref "U3") (pin "P$110") (pinfunction "SIM2_VDD_P$110") (pintype "bidirectional"))
    )
    (net (code "87") (name "unconnected-(U3-SIM_DET-PadP$34)") (class "Default")
      (node (ref "U3") (pin "P$34") (pinfunction "SIM_DET_P$34") (pintype "bidirectional"))
    )
    (net (code "88") (name "unconnected-(U3-SPI_CLK-PadP$11)") (class "Default")
      (node (ref "U3") (pin "P$11") (pinfunction "SPI_CLK_P$11") (pintype "bidirectional"))
    )
    (net (code "89") (name "unconnected-(U3-SPI_CS-PadP$12)") (class "Default")
      (node (ref "U3") (pin "P$12") (pinfunction "SPI_CS_P$12") (pintype "bidirectional"))
    )
    (net (code "90") (name "unconnected-(U3-SPI_MISO-PadP$14)") (class "Default")
      (node (ref "U3") (pin "P$14") (pinfunction "SPI_MISO_P$14") (pintype "bidirectional"))
    )
    (net (code "91") (name "unconnected-(U3-SPI_MOSI-PadP$13)") (class "Default")
      (node (ref "U3") (pin "P$13") (pinfunction "SPI_MOSI_P$13") (pintype "bidirectional"))
    )
    (net (code "92") (name "unconnected-(U3-STATUS-PadP$66)") (class "Default")
      (node (ref "U3") (pin "P$66") (pinfunction "STATUS_P$66") (pintype "bidirectional"))
    )
    (net (code "93") (name "unconnected-(U3-U1_CTS-PadP$7)") (class "Default")
      (node (ref "U3") (pin "P$7") (pinfunction "U1_CTS_P$7") (pintype "bidirectional"))
    )
    (net (code "94") (name "unconnected-(U3-U1_DCD-PadP$5)") (class "Default")
      (node (ref "U3") (pin "P$5") (pinfunction "U1_DCD_P$5") (pintype "bidirectional"))
    )
    (net (code "95") (name "unconnected-(U3-U1_DTR-PadP$3)") (class "Default")
      (node (ref "U3") (pin "P$3") (pinfunction "U1_DTR_P$3") (pintype "bidirectional"))
    )
    (net (code "96") (name "unconnected-(U3-U1_RI-PadP$4)") (class "Default")
      (node (ref "U3") (pin "P$4") (pinfunction "U1_RI_P$4") (pintype "bidirectional"))
    )
    (net (code "97") (name "unconnected-(U3-U1_RTS-PadP$8)") (class "Default")
      (node (ref "U3") (pin "P$8") (pinfunction "U1_RTS_P$8") (pintype "bidirectional"))
    )
    (net (code "98") (name "unconnected-(U3-UART_LOG_RX-PadP$22)") (class "Default")
      (node (ref "U3") (pin "P$22") (pinfunction "UART_LOG_RX_P$22") (pintype "bidirectional"))
    )
    (net (code "99") (name "unconnected-(U3-UART_LOG_TX-PadP$23)") (class "Default")
      (node (ref "U3") (pin "P$23") (pinfunction "UART_LOG_TX_P$23") (pintype "bidirectional"))
    )
    (net (code "100") (name "unconnected-(U3-VBAT_ADC-PadP$51)") (class "Default")
      (node (ref "U3") (pin "P$51") (pinfunction "VBAT_ADC_P$51") (pintype "bidirectional"))
    )
    (net (code "101") (name "unconnected-(U3-VDD_2V8-PadP$99)") (class "Default")
      (node (ref "U3") (pin "P$99") (pinfunction "VDD_2V8_P$99") (pintype "bidirectional"))
    )
  )
)
